# voice_launch.net
KiCad netlist of a schematic drawn in Altium Designer
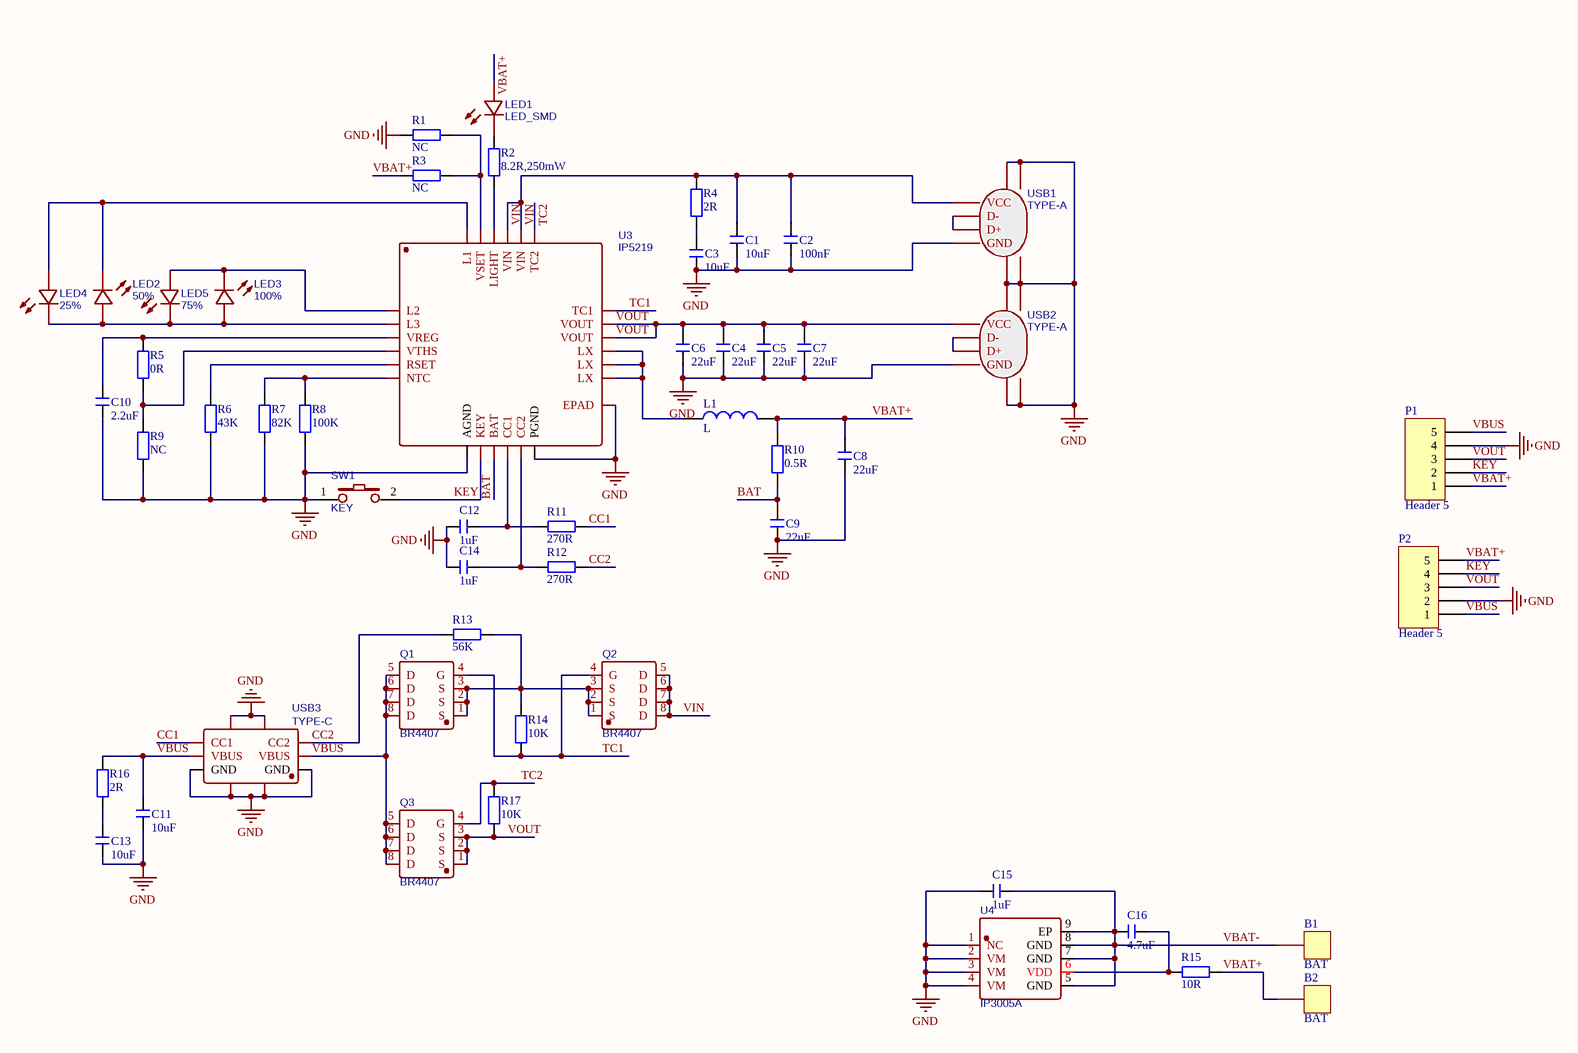
[diagram p0: voice_launch.SchDoc]

(export (version "E")
  (design (tool "Eeschema 10.0.6"))
  (components
    (comp (ref "B1") (value "BAT") (footprint "BAT") (libsource (lib "voice_launch") (part "BAT")))
    (comp (ref "B2") (value "BAT") (footprint "BAT") (libsource (lib "voice_launch") (part "BAT")))
    (comp (ref "C1")
      (value "10uF")
      (footprint "C0603")
      (description "无极性贴片电容")
      (fields (field (name "版权归属") "源创客"))
      (libsource (lib "voice_launch") (part "Cap"))
    )
    (comp (ref "C2")
      (value "100nF")
      (footprint "C0603")
      (description "无极性贴片电容")
      (fields (field (name "版权归属") "源创客"))
      (libsource (lib "voice_launch") (part "Cap"))
    )
    (comp (ref "C3")
      (value "10uF")
      (footprint "C0603")
      (description "无极性贴片电容")
      (fields (field (name "版权归属") "源创客"))
      (libsource (lib "voice_launch") (part "Cap"))
    )
    (comp (ref "C4")
      (value "22uF")
      (footprint "C0603")
      (description "无极性贴片电容")
      (fields (field (name "版权归属") "源创客"))
      (libsource (lib "voice_launch") (part "Cap"))
    )
    (comp (ref "C5")
      (value "22uF")
      (footprint "C0603")
      (description "无极性贴片电容")
      (fields (field (name "版权归属") "源创客"))
      (libsource (lib "voice_launch") (part "Cap"))
    )
    (comp (ref "C6")
      (value "22uF")
      (footprint "C0603")
      (description "无极性贴片电容")
      (fields (field (name "版权归属") "源创客"))
      (libsource (lib "voice_launch") (part "Cap"))
    )
    (comp (ref "C7")
      (value "22uF")
      (footprint "C0603")
      (description "无极性贴片电容")
      (fields (field (name "版权归属") "源创客"))
      (libsource (lib "voice_launch") (part "Cap"))
    )
    (comp (ref "C8")
      (value "22uF")
      (footprint "C0603")
      (description "无极性贴片电容")
      (fields (field (name "版权归属") "源创客"))
      (libsource (lib "voice_launch") (part "Cap"))
    )
    (comp (ref "C9")
      (value "22uF")
      (footprint "C0603")
      (description "无极性贴片电容")
      (fields (field (name "版权归属") "源创客"))
      (libsource (lib "voice_launch") (part "Cap"))
    )
    (comp (ref "C10")
      (value "2.2uF")
      (footprint "C0603")
      (description "无极性贴片电容")
      (fields (field (name "版权归属") "源创客"))
      (libsource (lib "voice_launch") (part "Cap"))
    )
    (comp (ref "C11")
      (value "10uF")
      (footprint "C0603")
      (description "无极性贴片电容")
      (fields (field (name "版权归属") "源创客"))
      (libsource (lib "voice_launch") (part "Cap"))
    )
    (comp (ref "C12")
      (value "1uF")
      (footprint "C0603")
      (description "无极性贴片电容")
      (fields (field (name "版权归属") "源创客"))
      (libsource (lib "voice_launch") (part "Cap"))
    )
    (comp (ref "C13")
      (value "10uF")
      (footprint "C0603")
      (description "无极性贴片电容")
      (fields (field (name "版权归属") "源创客"))
      (libsource (lib "voice_launch") (part "Cap"))
    )
    (comp (ref "C14")
      (value "1uF")
      (footprint "C0603")
      (description "无极性贴片电容")
      (fields (field (name "版权归属") "源创客"))
      (libsource (lib "voice_launch") (part "Cap"))
    )
    (comp (ref "C15")
      (value "1uF")
      (footprint "C0805")
      (description "无极性贴片电容")
      (fields (field (name "版权归属") "源创客"))
      (libsource (lib "voice_launch") (part "Cap"))
    )
    (comp (ref "C16")
      (value "4.7uF")
      (footprint "C0805")
      (description "无极性贴片电容")
      (fields (field (name "版权归属") "源创客"))
      (libsource (lib "voice_launch") (part "Cap"))
    )
    (comp (ref "L1")
      (value "L")
      (footprint "IND-SMD")
      (description "小功率贴片电感")
      (fields (field (name "版权归属") "源创客"))
      (libsource (lib "voice_launch") (part "L"))
    )
    (comp (ref "LED1")
      (value "LED_SMD")
      (footprint "LED-SMD")
      (fields
        (field (name "BOM_SUPPLIER PART") "C193901")
        (field (name "BOM_MANUFACTURER PART") "FC-1608GHK-570A08")
        (field (name "CONTRIBUTOR") "LCSC")
      )
      (libsource (lib "voice_launch") (part "LED_SMD"))
    )
    (comp (ref "LED2")
      (value "50%")
      (footprint "LED0603")
      (description "LED0603")
      (fields
        (field (name "BOM_SUPPLIER PART") "C193901")
        (field (name "BOM_MANUFACTURER PART") "FC-1608GHK-570A08")
        (field (name "CONTRIBUTOR") "LCSC")
      )
      (libsource (lib "voice_launch") (part "LED"))
    )
    (comp (ref "LED3")
      (value "100%")
      (footprint "LED0603")
      (description "LED0603")
      (fields
        (field (name "BOM_SUPPLIER PART") "C193901")
        (field (name "BOM_MANUFACTURER PART") "FC-1608GHK-570A08")
        (field (name "CONTRIBUTOR") "LCSC")
      )
      (libsource (lib "voice_launch") (part "LED"))
    )
    (comp (ref "LED4")
      (value "25%")
      (footprint "LED0603")
      (description "LED0603")
      (fields
        (field (name "BOM_SUPPLIER PART") "C193901")
        (field (name "BOM_MANUFACTURER PART") "FC-1608GHK-570A08")
        (field (name "CONTRIBUTOR") "LCSC")
      )
      (libsource (lib "voice_launch") (part "LED"))
    )
    (comp (ref "LED5")
      (value "75%")
      (footprint "LED0603")
      (description "LED0603")
      (fields
        (field (name "BOM_SUPPLIER PART") "C193901")
        (field (name "BOM_MANUFACTURER PART") "FC-1608GHK-570A08")
        (field (name "CONTRIBUTOR") "LCSC")
      )
      (libsource (lib "voice_launch") (part "LED"))
    )
    (comp (ref "P1")
      (value "Header 5")
      (footprint "CONN-TH_S5B-PH-K-S-LF-SN")
      (description "Header, 5-Pin")
      (fields (field (name "PUBLISHER") "Altium Limited"))
      (libsource (lib "Miscellaneous Connectors") (part "Header 5"))
    )
    (comp (ref "P2")
      (value "Header 5")
      (footprint "CONN-TH_B6B-PH-K-S")
      (description "Header, 5-Pin")
      (fields (field (name "PUBLISHER") "Altium Limited"))
      (libsource (lib "Miscellaneous Connectors") (part "Header 5"))
    )
    (comp (ref "Q1")
      (value "BR4407")
      (footprint "PMOS-SOP-8")
      (description "C328572")
      (fields (field (name "CONTRIBUTOR") "LCSC"))
      (libsource (lib "voice_launch") (part "BR4407"))
    )
    (comp (ref "Q2")
      (value "BR4407")
      (footprint "PMOS-SOP-8")
      (description "C328572")
      (fields (field (name "CONTRIBUTOR") "LCSC"))
      (libsource (lib "voice_launch") (part "BR4407"))
    )
    (comp (ref "Q3")
      (value "BR4407")
      (footprint "PMOS-SOP-8")
      (description "C328572")
      (fields (field (name "CONTRIBUTOR") "LCSC"))
      (libsource (lib "voice_launch") (part "BR4407"))
    )
    (comp (ref "R1")
      (value "NC")
      (footprint "R0603")
      (description "贴片电阻")
      (fields (field (name "版权归属") "源创客"))
      (libsource (lib "voice_launch") (part "RES"))
    )
    (comp (ref "R2")
      (value "8.2R,250mW")
      (footprint "R0603")
      (description "贴片电阻")
      (fields (field (name "版权归属") "源创客"))
      (libsource (lib "voice_launch") (part "RES"))
    )
    (comp (ref "R3")
      (value "NC")
      (footprint "R0603")
      (description "贴片电阻")
      (fields (field (name "版权归属") "源创客"))
      (libsource (lib "voice_launch") (part "RES"))
    )
    (comp (ref "R4")
      (value "2R")
      (footprint "R0603")
      (description "贴片电阻")
      (fields (field (name "版权归属") "源创客"))
      (libsource (lib "voice_launch") (part "RES"))
    )
    (comp (ref "R5")
      (value "0R")
      (footprint "R0603")
      (description "贴片电阻")
      (fields (field (name "版权归属") "源创客"))
      (libsource (lib "voice_launch") (part "RES"))
    )
    (comp (ref "R6")
      (value "43K")
      (footprint "R0603")
      (description "贴片电阻")
      (fields (field (name "版权归属") "源创客"))
      (libsource (lib "voice_launch") (part "RES"))
    )
    (comp (ref "R7")
      (value "82K")
      (footprint "R0603")
      (description "贴片电阻")
      (fields (field (name "版权归属") "源创客"))
      (libsource (lib "voice_launch") (part "RES"))
    )
    (comp (ref "R8")
      (value "100K")
      (footprint "R0603")
      (description "贴片电阻")
      (fields (field (name "版权归属") "源创客"))
      (libsource (lib "voice_launch") (part "RES"))
    )
    (comp (ref "R9")
      (value "NC")
      (footprint "R0603")
      (description "贴片电阻")
      (fields (field (name "版权归属") "源创客"))
      (libsource (lib "voice_launch") (part "RES"))
    )
    (comp (ref "R10")
      (value "0.5R")
      (footprint "R0603")
      (description "贴片电阻")
      (fields (field (name "版权归属") "源创客"))
      (libsource (lib "voice_launch") (part "RES"))
    )
    (comp (ref "R11")
      (value "270R")
      (footprint "R0603")
      (description "贴片电阻")
      (fields (field (name "版权归属") "源创客"))
      (libsource (lib "voice_launch") (part "RES"))
    )
    (comp (ref "R12")
      (value "270R")
      (footprint "R0603")
      (description "贴片电阻")
      (fields (field (name "版权归属") "源创客"))
      (libsource (lib "voice_launch") (part "RES"))
    )
    (comp (ref "R13")
      (value "56K")
      (footprint "R0603")
      (description "贴片电阻")
      (fields (field (name "版权归属") "源创客"))
      (libsource (lib "voice_launch") (part "RES"))
    )
    (comp (ref "R14")
      (value "10K")
      (footprint "R0603")
      (description "贴片电阻")
      (fields (field (name "版权归属") "源创客"))
      (libsource (lib "voice_launch") (part "RES"))
    )
    (comp (ref "R15")
      (value "10R")
      (footprint "R0805")
      (description "贴片电阻")
      (fields (field (name "版权归属") "源创客"))
      (libsource (lib "voice_launch") (part "RES"))
    )
    (comp (ref "R16")
      (value "2R")
      (footprint "R0603")
      (description "贴片电阻")
      (fields (field (name "版权归属") "源创客"))
      (libsource (lib "voice_launch") (part "RES"))
    )
    (comp (ref "R17")
      (value "10K")
      (footprint "R0603")
      (description "贴片电阻")
      (fields (field (name "版权归属") "源创客"))
      (libsource (lib "voice_launch") (part "RES"))
    )
    (comp (ref "SW1")
      (value "KEY")
      (footprint "SW-SMD_TS24CA")
      (fields
        (field (name "BOM_SUPPLIER PART") "C223741")
        (field (name "BOM_MANUFACTURER PART") "K2-6639SP-V4SC-04")
        (field (name "CONTRIBUTOR") "LCSC")
      )
      (libsource (lib "voice_launch") (part "KEY"))
    )
    (comp (ref "U3")
      (value "IP5219")
      (footprint "QFN-24")
      (description "充放电升压模块")
      (fields (field (name "BOM_SUPPLIER PART") "C181694") (field (name "CONTRIBUTOR") "LCSC"))
      (libsource (lib "voice_launch") (part "IP5219"))
    )
    (comp (ref "U4")
      (value "IP3005A")
      (footprint "IP3005A")
      (fields (field (name "BOM_SUPPLIER PART") "C181685") (field (name "CONTRIBUTOR") "LCSC"))
      (libsource (lib "voice_launch") (part "IP3005A"))
    )
    (comp (ref "USB1")
      (value "TYPE-A")
      (footprint "USB-A")
      (fields
        (field (name "BOM_MANUFACTURER PART") "A/FPaste board Dparagraph10Four feet without curling ironLCPVinyl6.8Reverse")
        (field (name "BOM_SUPPLIER PART") "C42474")
      )
      (libsource (lib "voice_launch") (part "TYPE-A"))
    )
    (comp (ref "USB2")
      (value "TYPE-A")
      (footprint "USB-A")
      (fields
        (field (name "BOM_MANUFACTURER PART") "A/FPaste board Dparagraph10Four feet without curling ironLCPVinyl6.8Reverse")
        (field (name "BOM_SUPPLIER PART") "C42474")
      )
      (libsource (lib "voice_launch") (part "TYPE-A"))
    )
    (comp (ref "USB3")
      (value "TYPE-C")
      (footprint "TYPE-C")
      (description "TYPE-C\r\n¦C2764612")
      (fields
        (field (name "BOM_SUPPLIER PART") "C2764612")
        (field (name "BOM_MANUFACTURER PART") "U262-061N-4BVC11")
        (field (name "CONTRIBUTOR") "LCSC")
      )
      (libsource (lib "voice_launch") (part "TYPE-C"))
    )
  )
  (nets
    (net (code "1") (name "/BAT") (class "Default")
      (node (ref "C9") (pin "2") (pinfunction "2_2") (pintype "passive"))
      (node (ref "R10") (pin "1") (pinfunction "1_1") (pintype "passive"))
      (node (ref "U3") (pin "9") (pinfunction "BAT_9") (pintype "passive"))
    )
    (net (code "2") (name "/CC1") (class "Default")
      (node (ref "R11") (pin "1") (pinfunction "1_1") (pintype "passive"))
      (node (ref "USB3") (pin "A5") (pinfunction "CC1_A5") (pintype "passive"))
    )
    (net (code "3") (name "/CC2") (class "Default")
      (node (ref "R12") (pin "1") (pinfunction "1_1") (pintype "passive"))
      (node (ref "R13") (pin "2") (pinfunction "2_2") (pintype "passive"))
      (node (ref "USB3") (pin "B5") (pinfunction "CC2_B5") (pintype "passive"))
    )
    (net (code "4") (name "/KEY") (class "Default")
      (node (ref "P1") (pin "2") (pinfunction "2_2") (pintype "passive"))
      (node (ref "P2") (pin "4") (pinfunction "4_4") (pintype "passive"))
      (node (ref "SW1") (pin "2") (pinfunction "2_2") (pintype "passive"))
      (node (ref "U3") (pin "8") (pinfunction "KEY_8") (pintype "passive"))
    )
    (net (code "5") (name "/TC1") (class "Default")
      (node (ref "Q1") (pin "4") (pinfunction "G_4") (pintype "passive"))
      (node (ref "Q2") (pin "4") (pinfunction "G_4") (pintype "passive"))
      (node (ref "R14") (pin "1") (pinfunction "1_1") (pintype "passive"))
      (node (ref "U3") (pin "18") (pinfunction "TC1_18") (pintype "passive"))
    )
    (net (code "6") (name "/TC2") (class "Default")
      (node (ref "Q3") (pin "4") (pinfunction "G_4") (pintype "passive"))
      (node (ref "R17") (pin "2") (pinfunction "2_2") (pintype "passive"))
      (node (ref "U3") (pin "19") (pinfunction "TC2_19") (pintype "passive"))
    )
    (net (code "7") (name "/VBAT+") (class "Default")
      (node (ref "B2") (pin "1") (pinfunction "1_1") (pintype "passive"))
      (node (ref "C8") (pin "2") (pinfunction "2_2") (pintype "passive"))
      (node (ref "L1") (pin "2") (pinfunction "2_2") (pintype "passive"))
      (node (ref "LED1") (pin "1") (pinfunction "+_1") (pintype "passive"))
      (node (ref "P1") (pin "1") (pinfunction "1_1") (pintype "passive"))
      (node (ref "P2") (pin "5") (pinfunction "5_5") (pintype "passive"))
      (node (ref "R10") (pin "2") (pinfunction "2_2") (pintype "passive"))
      (node (ref "R15") (pin "1") (pinfunction "1_1") (pintype "passive"))
      (node (ref "R3") (pin "2") (pinfunction "2_2") (pintype "passive"))
    )
    (net (code "8") (name "/VBAT-") (class "Default")
      (node (ref "B1") (pin "1") (pinfunction "1_1") (pintype "passive"))
      (node (ref "C15") (pin "1") (pinfunction "1_1") (pintype "passive"))
      (node (ref "C16") (pin "2") (pinfunction "2_2") (pintype "passive"))
      (node (ref "U4") (pin "5") (pinfunction "GND_5") (pintype "passive"))
      (node (ref "U4") (pin "7") (pinfunction "GND_7") (pintype "passive"))
      (node (ref "U4") (pin "8") (pinfunction "GND_8") (pintype "passive"))
      (node (ref "U4") (pin "9") (pinfunction "EP_9") (pintype "passive"))
    )
    (net (code "9") (name "/VBUS") (class "Default")
      (node (ref "C11") (pin "2") (pinfunction "2_2") (pintype "passive"))
      (node (ref "P1") (pin "5") (pinfunction "5_5") (pintype "passive"))
      (node (ref "P2") (pin "1") (pinfunction "1_1") (pintype "passive"))
      (node (ref "Q1") (pin "5") (pinfunction "D_5") (pintype "passive"))
      (node (ref "Q1") (pin "6") (pinfunction "D_6") (pintype "passive"))
      (node (ref "Q1") (pin "7") (pinfunction "D_7") (pintype "passive"))
      (node (ref "Q1") (pin "8") (pinfunction "D_8") (pintype "passive"))
      (node (ref "Q3") (pin "5") (pinfunction "D_5") (pintype "passive"))
      (node (ref "Q3") (pin "6") (pinfunction "D_6") (pintype "passive"))
      (node (ref "Q3") (pin "7") (pinfunction "D_7") (pintype "passive"))
      (node (ref "Q3") (pin "8") (pinfunction "D_8") (pintype "passive"))
      (node (ref "R16") (pin "1") (pinfunction "1_1") (pintype "passive"))
      (node (ref "USB3") (pin "A9") (pinfunction "VBUS_A9") (pintype "passive"))
      (node (ref "USB3") (pin "B9") (pinfunction "VBUS_B9") (pintype "passive"))
    )
    (net (code "10") (name "/VIN") (class "Default")
      (node (ref "C1") (pin "2") (pinfunction "2_2") (pintype "passive"))
      (node (ref "C2") (pin "2") (pinfunction "2_2") (pintype "passive"))
      (node (ref "Q2") (pin "5") (pinfunction "D_5") (pintype "passive"))
      (node (ref "Q2") (pin "6") (pinfunction "D_6") (pintype "passive"))
      (node (ref "Q2") (pin "7") (pinfunction "D_7") (pintype "passive"))
      (node (ref "Q2") (pin "8") (pinfunction "D_8") (pintype "passive"))
      (node (ref "R4") (pin "2") (pinfunction "2_2") (pintype "passive"))
      (node (ref "U3") (pin "20") (pinfunction "VIN_20") (pintype "passive"))
      (node (ref "U3") (pin "21") (pinfunction "VIN_21") (pintype "passive"))
      (node (ref "USB1") (pin "1") (pinfunction "VCC_1") (pintype "passive"))
    )
    (net (code "11") (name "/VOUT") (class "Default")
      (node (ref "C4") (pin "2") (pinfunction "2_2") (pintype "passive"))
      (node (ref "C5") (pin "2") (pinfunction "2_2") (pintype "passive"))
      (node (ref "C6") (pin "2") (pinfunction "2_2") (pintype "passive"))
      (node (ref "C7") (pin "2") (pinfunction "2_2") (pintype "passive"))
      (node (ref "P1") (pin "3") (pinfunction "3_3") (pintype "passive"))
      (node (ref "P2") (pin "3") (pinfunction "3_3") (pintype "passive"))
      (node (ref "Q3") (pin "1") (pinfunction "S_1") (pintype "passive"))
      (node (ref "Q3") (pin "2") (pinfunction "S_2") (pintype "passive"))
      (node (ref "Q3") (pin "3") (pinfunction "S_3") (pintype "passive"))
      (node (ref "R17") (pin "1") (pinfunction "1_1") (pintype "passive"))
      (node (ref "U3") (pin "16") (pinfunction "VOUT_16") (pintype "passive"))
      (node (ref "U3") (pin "17") (pinfunction "VOUT_17") (pintype "passive"))
      (node (ref "USB2") (pin "1") (pinfunction "VCC_1") (pintype "passive"))
    )
    (net (code "12") (name "GND") (class "Default")
      (node (ref "C1") (pin "1") (pinfunction "1_1") (pintype "passive"))
      (node (ref "C10") (pin "1") (pinfunction "1_1") (pintype "passive"))
      (node (ref "C11") (pin "1") (pinfunction "1_1") (pintype "passive"))
      (node (ref "C12") (pin "2") (pinfunction "2_2") (pintype "passive"))
      (node (ref "C13") (pin "1") (pinfunction "1_1") (pintype "passive"))
      (node (ref "C14") (pin "2") (pinfunction "2_2") (pintype "passive"))
      (node (ref "C15") (pin "2") (pinfunction "2_2") (pintype "passive"))
      (node (ref "C2") (pin "1") (pinfunction "1_1") (pintype "passive"))
      (node (ref "C3") (pin "1") (pinfunction "1_1") (pintype "passive"))
      (node (ref "C4") (pin "1") (pinfunction "1_1") (pintype "passive"))
      (node (ref "C5") (pin "1") (pinfunction "1_1") (pintype "passive"))
      (node (ref "C6") (pin "1") (pinfunction "1_1") (pintype "passive"))
      (node (ref "C7") (pin "1") (pinfunction "1_1") (pintype "passive"))
      (node (ref "C8") (pin "1") (pinfunction "1_1") (pintype "passive"))
      (node (ref "C9") (pin "1") (pinfunction "1_1") (pintype "passive"))
      (node (ref "P1") (pin "4") (pinfunction "4_4") (pintype "passive"))
      (node (ref "P2") (pin "2") (pinfunction "2_2") (pintype "passive"))
      (node (ref "R1") (pin "2") (pinfunction "2_2") (pintype "passive"))
      (node (ref "R6") (pin "1") (pinfunction "1_1") (pintype "passive"))
      (node (ref "R7") (pin "1") (pinfunction "1_1") (pintype "passive"))
      (node (ref "R8") (pin "1") (pinfunction "1_1") (pintype "passive"))
      (node (ref "R9") (pin "1") (pinfunction "1_1") (pintype "passive"))
      (node (ref "SW1") (pin "1") (pinfunction "1_1") (pintype "passive"))
      (node (ref "U3") (pin "12") (pinfunction "PGND_12") (pintype "passive"))
      (node (ref "U3") (pin "25") (pinfunction "EPAD_25") (pintype "passive"))
      (node (ref "U3") (pin "7") (pinfunction "AGND_7") (pintype "passive"))
      (node (ref "U4") (pin "1") (pinfunction "NC_1") (pintype "passive"))
      (node (ref "U4") (pin "2") (pinfunction "VM_2") (pintype "passive"))
      (node (ref "U4") (pin "3") (pinfunction "VM_3") (pintype "passive"))
      (node (ref "U4") (pin "4") (pinfunction "VM_4") (pintype "passive"))
      (node (ref "USB1") (pin "4") (pinfunction "GND_4") (pintype "passive"))
      (node (ref "USB1") (pin "5") (pinfunction "5_5") (pintype "passive"))
      (node (ref "USB1") (pin "6") (pinfunction "1_6") (pintype "passive"))
      (node (ref "USB1") (pin "7") (pinfunction "2_7") (pintype "passive"))
      (node (ref "USB1") (pin "8") (pinfunction "3_8") (pintype "passive"))
      (node (ref "USB2") (pin "4") (pinfunction "GND_4") (pintype "passive"))
      (node (ref "USB2") (pin "5") (pinfunction "5_5") (pintype "passive"))
      (node (ref "USB2") (pin "6") (pinfunction "1_6") (pintype "passive"))
      (node (ref "USB2") (pin "7") (pinfunction "2_7") (pintype "passive"))
      (node (ref "USB2") (pin "8") (pinfunction "3_8") (pintype "passive"))
      (node (ref "USB3") (pin "10") (pinfunction "10_10") (pintype "passive"))
      (node (ref "USB3") (pin "7") (pinfunction "7_7") (pintype "passive"))
      (node (ref "USB3") (pin "8") (pinfunction "8_8") (pintype "passive"))
      (node (ref "USB3") (pin "9") (pinfunction "9_9") (pintype "passive"))
      (node (ref "USB3") (pin "A12") (pinfunction "GND_A12") (pintype "passive"))
      (node (ref "USB3") (pin "B12") (pinfunction "GND_B12") (pintype "passive"))
    )
    (net (code "13") (name "Net-(C3-Pad2)") (class "Default")
      (node (ref "C3") (pin "2") (pinfunction "2_2") (pintype "passive"))
      (node (ref "R4") (pin "1") (pinfunction "1_1") (pintype "passive"))
    )
    (net (code "14") (name "Net-(C13-Pad2)") (class "Default")
      (node (ref "C13") (pin "2") (pinfunction "2_2") (pintype "passive"))
      (node (ref "R16") (pin "2") (pinfunction "2_2") (pintype "passive"))
    )
    (net (code "15") (name "Net-(L1-Pad1)") (class "Default")
      (node (ref "L1") (pin "1") (pinfunction "1_1") (pintype "passive"))
      (node (ref "U3") (pin "13") (pinfunction "LX_13") (pintype "passive"))
      (node (ref "U3") (pin "14") (pinfunction "LX_14") (pintype "passive"))
      (node (ref "U3") (pin "15") (pinfunction "LX_15") (pintype "passive"))
    )
    (net (code "16") (name "Net-(LED1--)") (class "Default")
      (node (ref "LED1") (pin "2") (pinfunction "-_2") (pintype "passive"))
      (node (ref "R2") (pin "2") (pinfunction "2_2") (pintype "passive"))
    )
    (net (code "17") (name "Net-(LED2-+)") (class "Default")
      (node (ref "LED2") (pin "1") (pinfunction "+_1") (pintype "passive"))
      (node (ref "LED3") (pin "1") (pinfunction "+_1") (pintype "passive"))
      (node (ref "LED4") (pin "2") (pinfunction "-_2") (pintype "passive"))
      (node (ref "LED5") (pin "2") (pinfunction "-_2") (pintype "passive"))
      (node (ref "U3") (pin "2") (pinfunction "L3_2") (pintype "passive"))
    )
    (net (code "18") (name "Net-(LED2--)") (class "Default")
      (node (ref "LED2") (pin "2") (pinfunction "-_2") (pintype "passive"))
      (node (ref "LED4") (pin "1") (pinfunction "+_1") (pintype "passive"))
      (node (ref "U3") (pin "24") (pinfunction "L1_24") (pintype "passive"))
    )
    (net (code "19") (name "Net-(LED3--)") (class "Default")
      (node (ref "LED3") (pin "2") (pinfunction "-_2") (pintype "passive"))
      (node (ref "LED5") (pin "1") (pinfunction "+_1") (pintype "passive"))
      (node (ref "U3") (pin "1") (pinfunction "L2_1") (pintype "passive"))
    )
    (net (code "20") (name "Net-(Q1-S-Pad1)") (class "Default")
      (node (ref "Q1") (pin "1") (pinfunction "S_1") (pintype "passive"))
      (node (ref "Q1") (pin "2") (pinfunction "S_2") (pintype "passive"))
      (node (ref "Q1") (pin "3") (pinfunction "S_3") (pintype "passive"))
      (node (ref "Q2") (pin "1") (pinfunction "S_1") (pintype "passive"))
      (node (ref "Q2") (pin "2") (pinfunction "S_2") (pintype "passive"))
      (node (ref "Q2") (pin "3") (pinfunction "S_3") (pintype "passive"))
      (node (ref "R13") (pin "1") (pinfunction "1_1") (pintype "passive"))
      (node (ref "R14") (pin "2") (pinfunction "2_2") (pintype "passive"))
    )
    (net (code "21") (name "Net-(U3-CC1)") (class "Default")
      (node (ref "C12") (pin "1") (pinfunction "1_1") (pintype "passive"))
      (node (ref "R11") (pin "2") (pinfunction "2_2") (pintype "passive"))
      (node (ref "U3") (pin "10") (pinfunction "CC1_10") (pintype "passive"))
    )
    (net (code "22") (name "Net-(U3-CC2)") (class "Default")
      (node (ref "C14") (pin "1") (pinfunction "1_1") (pintype "passive"))
      (node (ref "R12") (pin "2") (pinfunction "2_2") (pintype "passive"))
      (node (ref "U3") (pin "11") (pinfunction "CC2_11") (pintype "passive"))
    )
    (net (code "23") (name "Net-(U3-LIGHT)") (class "Default")
      (node (ref "R2") (pin "1") (pinfunction "1_1") (pintype "passive"))
      (node (ref "U3") (pin "22") (pinfunction "LIGHT_22") (pintype "passive"))
    )
    (net (code "24") (name "Net-(U3-NTC)") (class "Default")
      (node (ref "R7") (pin "2") (pinfunction "2_2") (pintype "passive"))
      (node (ref "R8") (pin "2") (pinfunction "2_2") (pintype "passive"))
      (node (ref "U3") (pin "6") (pinfunction "NTC_6") (pintype "passive"))
    )
    (net (code "25") (name "Net-(U3-RSET)") (class "Default")
      (node (ref "R6") (pin "2") (pinfunction "2_2") (pintype "passive"))
      (node (ref "U3") (pin "5") (pinfunction "RSET_5") (pintype "passive"))
    )
    (net (code "26") (name "Net-(U3-VREG)") (class "Default")
      (node (ref "C10") (pin "2") (pinfunction "2_2") (pintype "passive"))
      (node (ref "R5") (pin "2") (pinfunction "2_2") (pintype "passive"))
      (node (ref "U3") (pin "3") (pinfunction "VREG_3") (pintype "passive"))
    )
    (net (code "27") (name "Net-(U3-VSET)") (class "Default")
      (node (ref "R1") (pin "1") (pinfunction "1_1") (pintype "passive"))
      (node (ref "R3") (pin "1") (pinfunction "1_1") (pintype "passive"))
      (node (ref "U3") (pin "23") (pinfunction "VSET_23") (pintype "passive"))
    )
    (net (code "28") (name "Net-(U3-VTHS)") (class "Default")
      (node (ref "R5") (pin "1") (pinfunction "1_1") (pintype "passive"))
      (node (ref "R9") (pin "2") (pinfunction "2_2") (pintype "passive"))
      (node (ref "U3") (pin "4") (pinfunction "VTHS_4") (pintype "passive"))
    )
    (net (code "29") (name "Net-(U4-VDD)") (class "Default")
      (node (ref "C16") (pin "1") (pinfunction "1_1") (pintype "passive"))
      (node (ref "R15") (pin "2") (pinfunction "2_2") (pintype "passive"))
      (node (ref "U4") (pin "6") (pinfunction "VDD_6") (pintype "passive"))
    )
    (net (code "30") (name "Net-(USB1-D+)") (class "Default")
      (node (ref "USB1") (pin "2") (pinfunction "D-_2") (pintype "passive"))
      (node (ref "USB1") (pin "3") (pinfunction "D+_3") (pintype "passive"))
    )
    (net (code "31") (name "Net-(USB2-D+)") (class "Default")
      (node (ref "USB2") (pin "2") (pinfunction "D-_2") (pintype "passive"))
      (node (ref "USB2") (pin "3") (pinfunction "D+_3") (pintype "passive"))
    )
  )
)
